# Bartosz_Nowakowski.net
KiCad netlist of a schematic drawn in EAGLE
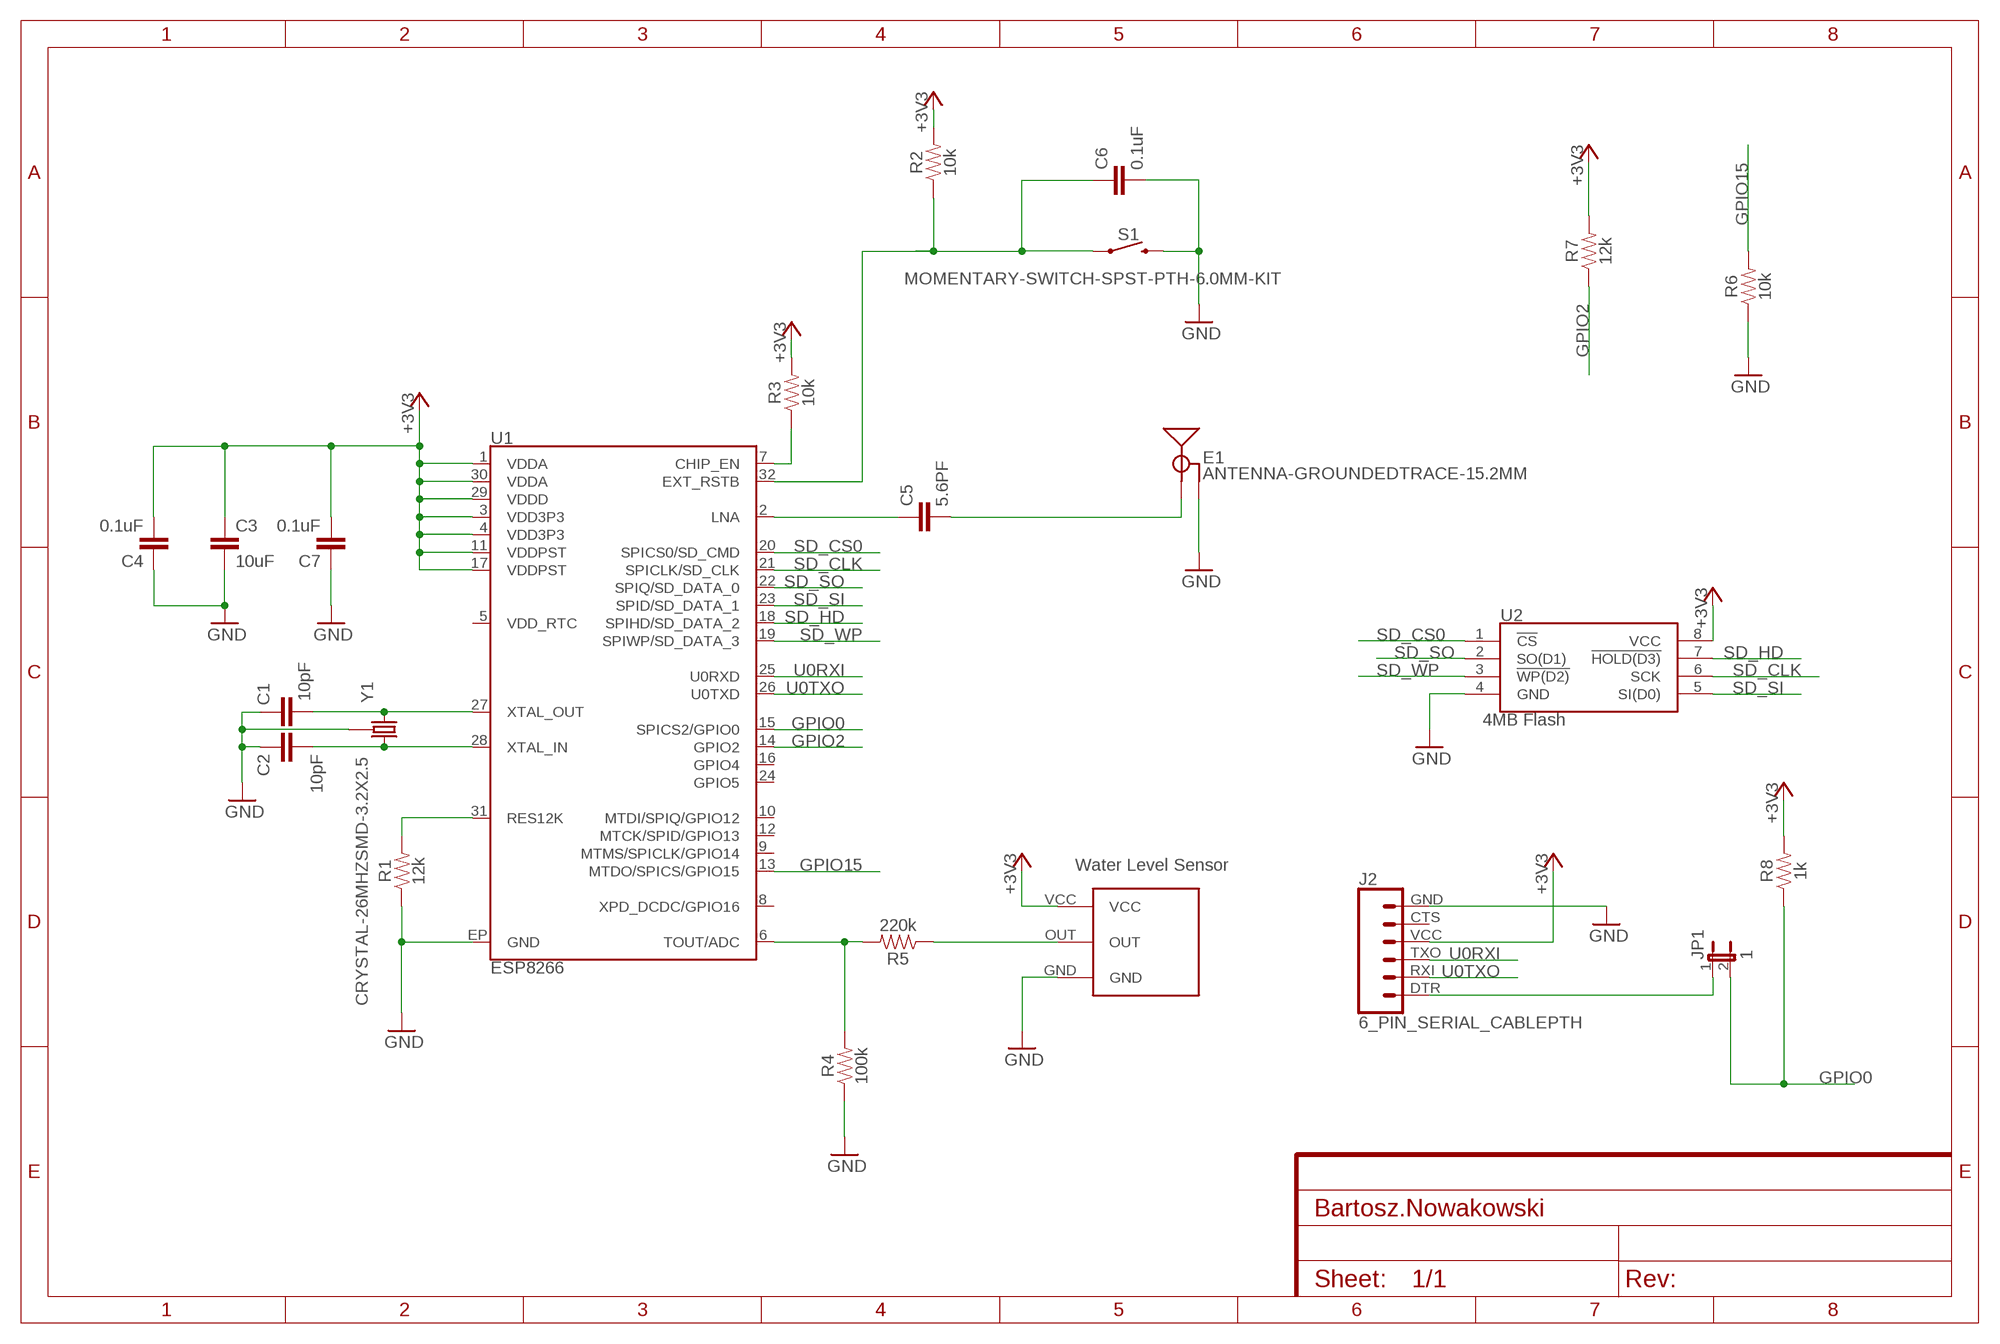
[diagram p0: schematic, sheet 1]

(export (version "E")
  (design (tool "Eeschema 10.0.6"))
  (components
    (comp (ref "C1")
      (value "10pF")
      (footprint "eagle-import:0603")
      (libsource (lib "eagle-import") (part "10PF-0603-50V-5%"))
    )
    (comp (ref "C2")
      (value "10pF")
      (footprint "eagle-import:0603")
      (libsource (lib "eagle-import") (part "10PF-0603-50V-5%"))
    )
    (comp (ref "C3")
      (value "10uF")
      (footprint "eagle-import:0805")
      (libsource (lib "eagle-import") (part "10UF-0805-10V-10%"))
    )
    (comp (ref "C4")
      (value "0.1uF")
      (footprint "eagle-import:0603")
      (libsource (lib "eagle-import") (part "0.1UF-0603-25V-5%"))
    )
    (comp (ref "C5")
      (value "5.6PF")
      (footprint "eagle-import:0603")
      (libsource (lib "eagle-import") (part "5.6PF-0603-50V-5%"))
    )
    (comp (ref "C6")
      (value "0.1uF")
      (footprint "eagle-import:0603")
      (libsource (lib "eagle-import") (part "0.1UF-0603-25V-5%"))
    )
    (comp (ref "C7")
      (value "0.1uF")
      (footprint "eagle-import:0603")
      (libsource (lib "eagle-import") (part "0.1UF-0603-25V-5%"))
    )
    (comp (ref "E1")
      (value "ANTENNA-GROUNDEDTRACE-15.2MM")
      (footprint "eagle-import:TRACE_ANTENNA_2.4GHZ_15.2MM")
      (libsource (lib "eagle-import") (part "ANTENNA-GROUNDEDTRACE-15.2MM"))
    )
    (comp (ref "J2")
      (value "6_PIN_SERIAL_CABLEPTH")
      (footprint "eagle-import:FTDI_BASIC")
      (libsource (lib "eagle-import") (part "6_PIN_SERIAL_CABLEPTH"))
    )
    (comp (ref "JP1")
      (value "1")
      (footprint "eagle-import:JP1")
      (libsource (lib "eagle-import") (part "JP1E"))
    )
    (comp (ref "R1")
      (value "12k")
      (footprint "eagle-import:0603")
      (libsource (lib "eagle-import") (part "12KOHM-0603-1/10W-1%"))
    )
    (comp (ref "R2")
      (value "10k")
      (footprint "eagle-import:0603")
      (libsource (lib "eagle-import") (part "10KOHM-0603-1/10W-1%"))
    )
    (comp (ref "R3")
      (value "10k")
      (footprint "eagle-import:0603")
      (libsource (lib "eagle-import") (part "10KOHM-0603-1/10W-1%"))
    )
    (comp (ref "R4")
      (value "100k")
      (footprint "eagle-import:0603")
      (libsource (lib "eagle-import") (part "100KOHM-0603-1/10W-1%"))
    )
    (comp (ref "R5")
      (value "220k")
      (footprint "eagle-import:0603")
      (libsource (lib "eagle-import") (part "220KOHM-0603-1/10W-1%"))
    )
    (comp (ref "R6")
      (value "10k")
      (footprint "eagle-import:0603")
      (libsource (lib "eagle-import") (part "10KOHM-0603-1/10W-1%"))
    )
    (comp (ref "R7")
      (value "12k")
      (footprint "eagle-import:0603")
      (libsource (lib "eagle-import") (part "12KOHM-0603-1/10W-1%"))
    )
    (comp (ref "R8")
      (value "1k")
      (footprint "eagle-import:0603")
      (libsource (lib "eagle-import") (part "1KOHM-0603-1/10W-1%"))
    )
    (comp (ref "S1")
      (value "MOMENTARY-SWITCH-SPST-PTH-6.0MM-KIT")
      (footprint "eagle-import:TACTILE_SWITCH_PTH_6.0MM_KIT")
      (libsource (lib "eagle-import") (part "MOMENTARY-SWITCH-SPST-PTH-6.0MM-KIT"))
    )
    (comp (ref "U1")
      (value "ESP8266")
      (footprint "eagle-import:QFN32-5X5MM")
      (libsource (lib "eagle-import") (part "ESP8266"))
    )
    (comp (ref "U2")
      (value "4MB Flash")
      (footprint "eagle-import:SO08")
      (libsource (lib "eagle-import") (part "AT25SF041"))
    )
    (comp (ref "WATER1")
      (value "WATERLEVELSENORDEV")
      (footprint "eagle-import:WATERLEVELSENSORFT")
      (libsource (lib "eagle-import") (part "WATERLEVELSENORDEV"))
    )
    (comp (ref "Y1")
      (value "CRYSTAL-26MHZSMD-3.2X2.5")
      (footprint "eagle-import:CRYSTAL-SMD-3.2X2.5MM")
      (libsource (lib "eagle-import") (part "CRYSTAL-26MHZSMD-3.2X2.5"))
    )
  )
  (nets
    (net (code "1") (name "+3V3") (class "Default")
      (node (ref "C3") (pin "1") (pinfunction "1_1") (pintype "passive"))
      (node (ref "C4") (pin "2") (pinfunction "2_2") (pintype "passive"))
      (node (ref "C7") (pin "2") (pinfunction "2_2") (pintype "passive"))
      (node (ref "J2") (pin "VCC") (pinfunction "4_VCC") (pintype "passive"))
      (node (ref "R2") (pin "2") (pinfunction "2_2") (pintype "passive"))
      (node (ref "R3") (pin "2") (pinfunction "2_2") (pintype "passive"))
      (node (ref "R7") (pin "2") (pinfunction "2_2") (pintype "passive"))
      (node (ref "R8") (pin "2") (pinfunction "2_2") (pintype "passive"))
      (node (ref "U1") (pin "1") (pinfunction "VDDA_1") (pintype "bidirectional"))
      (node (ref "U1") (pin "11") (pinfunction "VDDPST_11") (pintype "bidirectional"))
      (node (ref "U1") (pin "17") (pinfunction "VDDPST_17") (pintype "bidirectional"))
      (node (ref "U1") (pin "29") (pinfunction "VDDD_29") (pintype "bidirectional"))
      (node (ref "U1") (pin "3") (pinfunction "VDD3P3_3") (pintype "bidirectional"))
      (node (ref "U1") (pin "30") (pinfunction "VDDA_30") (pintype "bidirectional"))
      (node (ref "U1") (pin "4") (pinfunction "VDD3P3_4") (pintype "bidirectional"))
      (node (ref "U2") (pin "8") (pinfunction "VCC_8") (pintype "bidirectional"))
      (node (ref "WATER1") (pin "VCC") (pinfunction "VCC_VCC") (pintype "bidirectional"))
    )
    (net (code "2") (name "/GPIO0") (class "Default")
      (node (ref "JP1") (pin "2") (pinfunction "2_2") (pintype "passive"))
      (node (ref "R8") (pin "1") (pinfunction "1_1") (pintype "passive"))
      (node (ref "U1") (pin "15") (pinfunction "SPICS2/GPIO0_15") (pintype "bidirectional"))
    )
    (net (code "3") (name "/GPIO2") (class "Default")
      (node (ref "R7") (pin "1") (pinfunction "1_1") (pintype "passive"))
      (node (ref "U1") (pin "14") (pinfunction "GPIO2_14") (pintype "bidirectional"))
    )
    (net (code "4") (name "/GPIO15") (class "Default")
      (node (ref "R6") (pin "2") (pinfunction "2_2") (pintype "passive"))
      (node (ref "U1") (pin "13") (pinfunction "MTDO/SPICS/GPIO15_13") (pintype "bidirectional"))
    )
    (net (code "5") (name "/SD_CLK") (class "Default")
      (node (ref "U1") (pin "21") (pinfunction "SPICLK/SD_CLK_21") (pintype "bidirectional"))
      (node (ref "U2") (pin "6") (pinfunction "SCK_6") (pintype "bidirectional"))
    )
    (net (code "6") (name "/SD_CS0") (class "Default")
      (node (ref "U1") (pin "20") (pinfunction "SPICS0/SD_CMD_20") (pintype "bidirectional"))
      (node (ref "U2") (pin "1") (pinfunction "~{CS}_1") (pintype "bidirectional"))
    )
    (net (code "7") (name "/SD_HD") (class "Default")
      (node (ref "U1") (pin "18") (pinfunction "SPIHD/SD_DATA_2_18") (pintype "bidirectional"))
      (node (ref "U2") (pin "7") (pinfunction "~{HOLD(D3})_7") (pintype "bidirectional"))
    )
    (net (code "8") (name "/SD_SI") (class "Default")
      (node (ref "U1") (pin "23") (pinfunction "SPID/SD_DATA_1_23") (pintype "bidirectional"))
      (node (ref "U2") (pin "5") (pinfunction "SI(D0)_5") (pintype "bidirectional"))
    )
    (net (code "9") (name "/SD_SO") (class "Default")
      (node (ref "U1") (pin "22") (pinfunction "SPIQ/SD_DATA_0_22") (pintype "bidirectional"))
      (node (ref "U2") (pin "2") (pinfunction "SO(D1)_2") (pintype "bidirectional"))
    )
    (net (code "10") (name "/SD_WP") (class "Default")
      (node (ref "U1") (pin "19") (pinfunction "SPIWP/SD_DATA_3_19") (pintype "bidirectional"))
      (node (ref "U2") (pin "3") (pinfunction "~{WP(D2})_3") (pintype "bidirectional"))
    )
    (net (code "11") (name "/U0RXI") (class "Default")
      (node (ref "J2") (pin "TXO") (pinfunction "3_TXO") (pintype "passive"))
      (node (ref "U1") (pin "25") (pinfunction "U0RXD_25") (pintype "bidirectional"))
    )
    (net (code "12") (name "/U0TXO") (class "Default")
      (node (ref "J2") (pin "RXI") (pinfunction "2_RXI") (pintype "passive"))
      (node (ref "U1") (pin "26") (pinfunction "U0TXD_26") (pintype "bidirectional"))
    )
    (net (code "13") (name "GND") (class "Default")
      (node (ref "C1") (pin "1") (pinfunction "1_1") (pintype "passive"))
      (node (ref "C2") (pin "1") (pinfunction "1_1") (pintype "passive"))
      (node (ref "C3") (pin "2") (pinfunction "2_2") (pintype "passive"))
      (node (ref "C4") (pin "1") (pinfunction "1_1") (pintype "passive"))
      (node (ref "C6") (pin "2") (pinfunction "2_2") (pintype "passive"))
      (node (ref "C7") (pin "1") (pinfunction "1_1") (pintype "passive"))
      (node (ref "E1") (pin "GND") (pinfunction "GND_GND") (pintype "bidirectional"))
      (node (ref "J2") (pin "GND") (pinfunction "6_GND") (pintype "passive"))
      (node (ref "R1") (pin "1") (pinfunction "1_1") (pintype "passive"))
      (node (ref "R4") (pin "1") (pinfunction "1_1") (pintype "passive"))
      (node (ref "R6") (pin "1") (pinfunction "1_1") (pintype "passive"))
      (node (ref "S1") (pin "3") (pinfunction "2_3") (pintype "passive"))
      (node (ref "U1") (pin "EP") (pinfunction "GND_EP") (pintype "bidirectional"))
      (node (ref "U2") (pin "4") (pinfunction "GND_4") (pintype "bidirectional"))
      (node (ref "WATER1") (pin "GND") (pinfunction "GND_GND") (pintype "bidirectional"))
      (node (ref "Y1") (pin "2") (pinfunction "3_2") (pintype "passive"))
      (node (ref "Y1") (pin "4") (pinfunction "3_4") (pintype "passive"))
    )
    (net (code "14") (name "Net-(E1-SIGNAL)") (class "Default")
      (node (ref "C5") (pin "2") (pinfunction "2_2") (pintype "passive"))
      (node (ref "E1") (pin "ANT") (pinfunction "SIGNAL_ANT") (pintype "bidirectional"))
    )
    (net (code "15") (name "Net-(J2-1)") (class "Default")
      (node (ref "J2") (pin "DTR") (pinfunction "1_DTR") (pintype "passive"))
      (node (ref "JP1") (pin "1") (pinfunction "1_1") (pintype "passive"))
    )
    (net (code "16") (name "Net-(R5-Pad1)") (class "Default")
      (node (ref "R5") (pin "1") (pinfunction "1_1") (pintype "passive"))
      (node (ref "WATER1") (pin "OUT") (pinfunction "OUT_OUT") (pintype "bidirectional"))
    )
    (net (code "17") (name "Net-(U1-CHIP_EN)") (class "Default")
      (node (ref "R3") (pin "1") (pinfunction "1_1") (pintype "passive"))
      (node (ref "U1") (pin "7") (pinfunction "CHIP_EN_7") (pintype "bidirectional"))
    )
    (net (code "18") (name "Net-(U1-EXT_RSTB)") (class "Default")
      (node (ref "C6") (pin "1") (pinfunction "1_1") (pintype "passive"))
      (node (ref "R2") (pin "1") (pinfunction "1_1") (pintype "passive"))
      (node (ref "S1") (pin "1") (pinfunction "1_1") (pintype "passive"))
      (node (ref "U1") (pin "32") (pinfunction "EXT_RSTB_32") (pintype "bidirectional"))
    )
    (net (code "19") (name "Net-(U1-LNA)") (class "Default")
      (node (ref "C5") (pin "1") (pinfunction "1_1") (pintype "passive"))
      (node (ref "U1") (pin "2") (pinfunction "LNA_2") (pintype "bidirectional"))
    )
    (net (code "20") (name "Net-(U1-RES12K)") (class "Default")
      (node (ref "R1") (pin "2") (pinfunction "2_2") (pintype "passive"))
      (node (ref "U1") (pin "31") (pinfunction "RES12K_31") (pintype "bidirectional"))
    )
    (net (code "21") (name "Net-(U1-TOUT{slash}ADC)") (class "Default")
      (node (ref "R4") (pin "2") (pinfunction "2_2") (pintype "passive"))
      (node (ref "R5") (pin "2") (pinfunction "2_2") (pintype "passive"))
      (node (ref "U1") (pin "6") (pinfunction "TOUT/ADC_6") (pintype "bidirectional"))
    )
    (net (code "22") (name "Net-(U1-XTAL_IN)") (class "Default")
      (node (ref "C2") (pin "2") (pinfunction "2_2") (pintype "passive"))
      (node (ref "U1") (pin "28") (pinfunction "XTAL_IN_28") (pintype "bidirectional"))
      (node (ref "Y1") (pin "3") (pinfunction "2_3") (pintype "passive"))
    )
    (net (code "23") (name "Net-(U1-XTAL_OUT)") (class "Default")
      (node (ref "C1") (pin "2") (pinfunction "2_2") (pintype "passive"))
      (node (ref "U1") (pin "27") (pinfunction "XTAL_OUT_27") (pintype "bidirectional"))
      (node (ref "Y1") (pin "1") (pinfunction "1_1") (pintype "passive"))
    )
    (net (code "24") (name "unconnected-(J2-5-PadCTS)") (class "Default")
      (node (ref "J2") (pin "CTS") (pinfunction "5_CTS") (pintype "passive"))
    )
    (net (code "25") (name "unconnected-(U1-GPIO4-Pad16)") (class "Default")
      (node (ref "U1") (pin "16") (pinfunction "GPIO4_16") (pintype "bidirectional"))
    )
    (net (code "26") (name "unconnected-(U1-GPIO5-Pad24)") (class "Default")
      (node (ref "U1") (pin "24") (pinfunction "GPIO5_24") (pintype "bidirectional"))
    )
    (net (code "27") (name "unconnected-(U1-MTCK{slash}SPID{slash}GPIO13-Pad12)") (class "Default")
      (node (ref "U1") (pin "12") (pinfunction "MTCK/SPID/GPIO13_12") (pintype "bidirectional"))
    )
    (net (code "28") (name "unconnected-(U1-MTDI{slash}SPIQ{slash}GPIO12-Pad10)") (class "Default")
      (node (ref "U1") (pin "10") (pinfunction "MTDI/SPIQ/GPIO12_10") (pintype "bidirectional"))
    )
    (net (code "29") (name "unconnected-(U1-MTMS{slash}SPICLK{slash}GPIO14-Pad9)") (class "Default")
      (node (ref "U1") (pin "9") (pinfunction "MTMS/SPICLK/GPIO14_9") (pintype "bidirectional"))
    )
    (net (code "30") (name "unconnected-(U1-VDD_RTC-Pad5)") (class "Default")
      (node (ref "U1") (pin "5") (pinfunction "VDD_RTC_5") (pintype "bidirectional"))
    )
    (net (code "31") (name "unconnected-(U1-XPD_DCDC{slash}GPIO16-Pad8)") (class "Default")
      (node (ref "U1") (pin "8") (pinfunction "XPD_DCDC/GPIO16_8") (pintype "bidirectional"))
    )
  )
)
